# kickstart_Adapter_Amiga500_Rev5.net
KiCad netlist of a schematic drawn in EAGLE
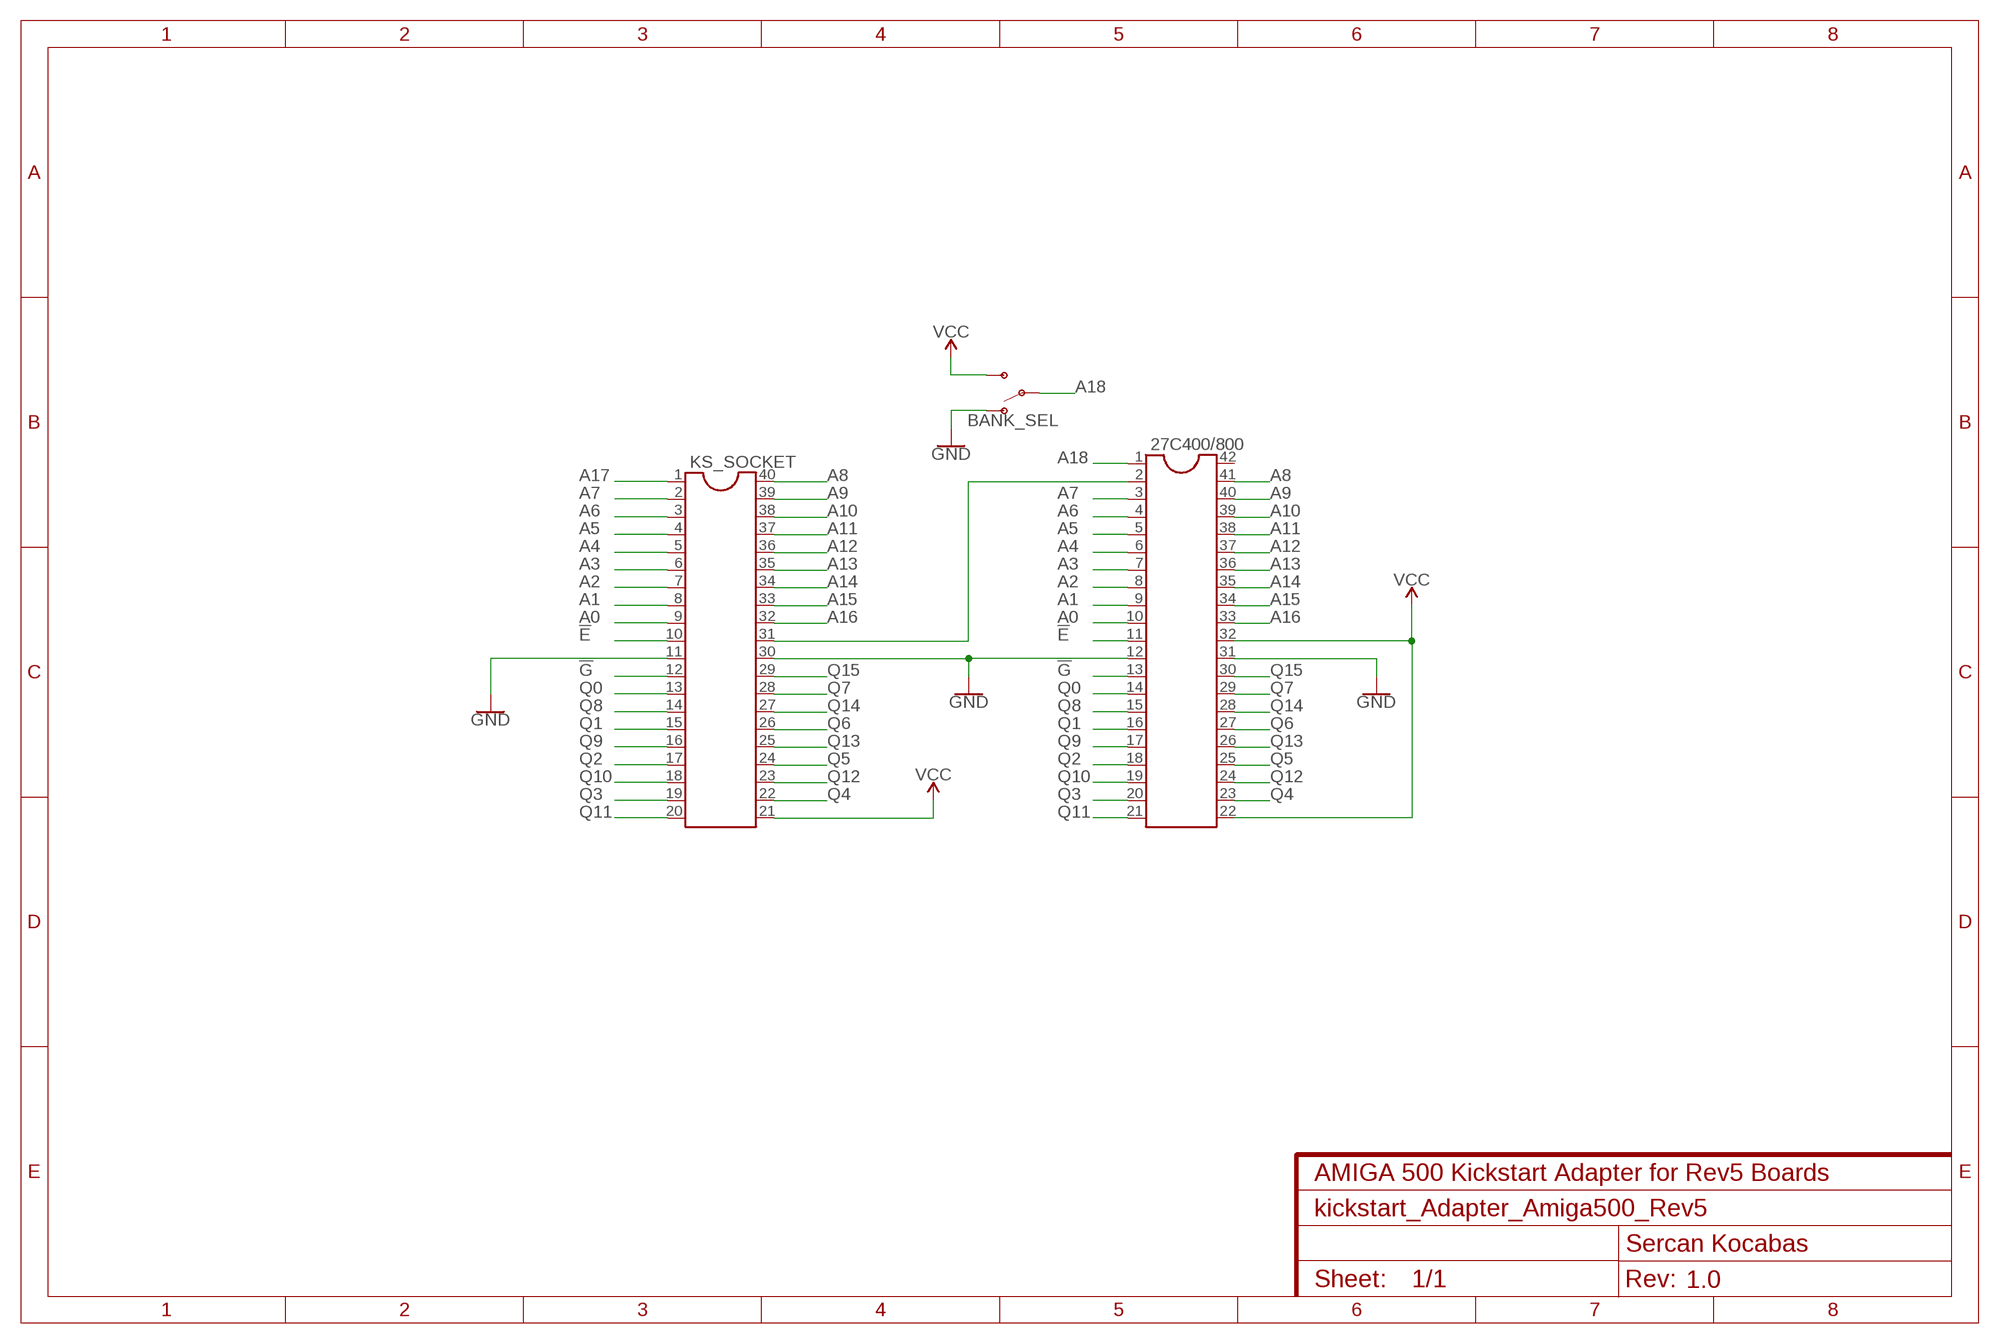
[diagram p0: schematic, sheet 1]

(export (version "E")
  (design (tool "Eeschema 10.0.6"))
  (components
    (comp (ref "27C400/800")
      (value "DIL42")
      (footprint "eagle-import:DIL42")
      (libsource (lib "eagle-import") (part "DIL42"))
    )
    (comp (ref "BANK_SEL")
      (value "SWITCH-SPDT-PTH-11.6X4.0MM")
      (footprint "eagle-import:SWITCH_SPDT_PTH_11.6X4.0MM")
      (libsource (lib "eagle-import") (part "SWITCH-SPDT-PTH-11.6X4.0MM"))
    )
    (comp (ref "KS_SOCKET")
      (value "DIL40")
      (footprint "eagle-import:DIL40")
      (libsource (lib "eagle-import") (part "DIL40"))
    )
  )
  (nets
    (net (code "1") (name "/A0") (class "Default")
      (node (ref "27C400/800") (pin "10") (pinfunction "10_10") (pintype "passive"))
      (node (ref "KS_SOCKET") (pin "9") (pinfunction "9_9") (pintype "passive"))
    )
    (net (code "2") (name "/A1") (class "Default")
      (node (ref "27C400/800") (pin "9") (pinfunction "9_9") (pintype "passive"))
      (node (ref "KS_SOCKET") (pin "8") (pinfunction "8_8") (pintype "passive"))
    )
    (net (code "3") (name "/A2") (class "Default")
      (node (ref "27C400/800") (pin "8") (pinfunction "8_8") (pintype "passive"))
      (node (ref "KS_SOCKET") (pin "7") (pinfunction "7_7") (pintype "passive"))
    )
    (net (code "4") (name "/A3") (class "Default")
      (node (ref "27C400/800") (pin "7") (pinfunction "7_7") (pintype "passive"))
      (node (ref "KS_SOCKET") (pin "6") (pinfunction "6_6") (pintype "passive"))
    )
    (net (code "5") (name "/A4") (class "Default")
      (node (ref "27C400/800") (pin "6") (pinfunction "6_6") (pintype "passive"))
      (node (ref "KS_SOCKET") (pin "5") (pinfunction "5_5") (pintype "passive"))
    )
    (net (code "6") (name "/A5") (class "Default")
      (node (ref "27C400/800") (pin "5") (pinfunction "5_5") (pintype "passive"))
      (node (ref "KS_SOCKET") (pin "4") (pinfunction "4_4") (pintype "passive"))
    )
    (net (code "7") (name "/A6") (class "Default")
      (node (ref "27C400/800") (pin "4") (pinfunction "4_4") (pintype "passive"))
      (node (ref "KS_SOCKET") (pin "3") (pinfunction "3_3") (pintype "passive"))
    )
    (net (code "8") (name "/A7") (class "Default")
      (node (ref "27C400/800") (pin "3") (pinfunction "3_3") (pintype "passive"))
      (node (ref "KS_SOCKET") (pin "2") (pinfunction "2_2") (pintype "passive"))
    )
    (net (code "9") (name "/A8") (class "Default")
      (node (ref "27C400/800") (pin "41") (pinfunction "41_41") (pintype "passive"))
      (node (ref "KS_SOCKET") (pin "40") (pinfunction "40_40") (pintype "passive"))
    )
    (net (code "10") (name "/A9") (class "Default")
      (node (ref "27C400/800") (pin "40") (pinfunction "40_40") (pintype "passive"))
      (node (ref "KS_SOCKET") (pin "39") (pinfunction "39_39") (pintype "passive"))
    )
    (net (code "11") (name "/A10") (class "Default")
      (node (ref "27C400/800") (pin "39") (pinfunction "39_39") (pintype "passive"))
      (node (ref "KS_SOCKET") (pin "38") (pinfunction "38_38") (pintype "passive"))
    )
    (net (code "12") (name "/A11") (class "Default")
      (node (ref "27C400/800") (pin "38") (pinfunction "38_38") (pintype "passive"))
      (node (ref "KS_SOCKET") (pin "37") (pinfunction "37_37") (pintype "passive"))
    )
    (net (code "13") (name "/A12") (class "Default")
      (node (ref "27C400/800") (pin "37") (pinfunction "37_37") (pintype "passive"))
      (node (ref "KS_SOCKET") (pin "36") (pinfunction "36_36") (pintype "passive"))
    )
    (net (code "14") (name "/A13") (class "Default")
      (node (ref "27C400/800") (pin "36") (pinfunction "36_36") (pintype "passive"))
      (node (ref "KS_SOCKET") (pin "35") (pinfunction "35_35") (pintype "passive"))
    )
    (net (code "15") (name "/A14") (class "Default")
      (node (ref "27C400/800") (pin "35") (pinfunction "35_35") (pintype "passive"))
      (node (ref "KS_SOCKET") (pin "34") (pinfunction "34_34") (pintype "passive"))
    )
    (net (code "16") (name "/A15") (class "Default")
      (node (ref "27C400/800") (pin "34") (pinfunction "34_34") (pintype "passive"))
      (node (ref "KS_SOCKET") (pin "33") (pinfunction "33_33") (pintype "passive"))
    )
    (net (code "17") (name "/A16") (class "Default")
      (node (ref "27C400/800") (pin "33") (pinfunction "33_33") (pintype "passive"))
      (node (ref "KS_SOCKET") (pin "32") (pinfunction "32_32") (pintype "passive"))
    )
    (net (code "18") (name "/A17") (class "Default")
      (node (ref "27C400/800") (pin "2") (pinfunction "2_2") (pintype "passive"))
      (node (ref "KS_SOCKET") (pin "1") (pinfunction "1_1") (pintype "passive"))
      (node (ref "KS_SOCKET") (pin "31") (pinfunction "31_31") (pintype "passive"))
    )
    (net (code "19") (name "/A18") (class "Default")
      (node (ref "27C400/800") (pin "1") (pinfunction "1_1") (pintype "passive"))
      (node (ref "BANK_SEL") (pin "2") (pinfunction "P_2") (pintype "passive"))
    )
    (net (code "20") (name "/Q0") (class "Default")
      (node (ref "27C400/800") (pin "14") (pinfunction "14_14") (pintype "passive"))
      (node (ref "KS_SOCKET") (pin "13") (pinfunction "13_13") (pintype "passive"))
    )
    (net (code "21") (name "/Q1") (class "Default")
      (node (ref "27C400/800") (pin "16") (pinfunction "16_16") (pintype "passive"))
      (node (ref "KS_SOCKET") (pin "15") (pinfunction "15_15") (pintype "passive"))
    )
    (net (code "22") (name "/Q2") (class "Default")
      (node (ref "27C400/800") (pin "18") (pinfunction "18_18") (pintype "passive"))
      (node (ref "KS_SOCKET") (pin "17") (pinfunction "17_17") (pintype "passive"))
    )
    (net (code "23") (name "/Q3") (class "Default")
      (node (ref "27C400/800") (pin "20") (pinfunction "20_20") (pintype "passive"))
      (node (ref "KS_SOCKET") (pin "19") (pinfunction "19_19") (pintype "passive"))
    )
    (net (code "24") (name "/Q4") (class "Default")
      (node (ref "27C400/800") (pin "23") (pinfunction "23_23") (pintype "passive"))
      (node (ref "KS_SOCKET") (pin "22") (pinfunction "22_22") (pintype "passive"))
    )
    (net (code "25") (name "/Q5") (class "Default")
      (node (ref "27C400/800") (pin "25") (pinfunction "25_25") (pintype "passive"))
      (node (ref "KS_SOCKET") (pin "24") (pinfunction "24_24") (pintype "passive"))
    )
    (net (code "26") (name "/Q6") (class "Default")
      (node (ref "27C400/800") (pin "27") (pinfunction "27_27") (pintype "passive"))
      (node (ref "KS_SOCKET") (pin "26") (pinfunction "26_26") (pintype "passive"))
    )
    (net (code "27") (name "/Q7") (class "Default")
      (node (ref "27C400/800") (pin "29") (pinfunction "29_29") (pintype "passive"))
      (node (ref "KS_SOCKET") (pin "28") (pinfunction "28_28") (pintype "passive"))
    )
    (net (code "28") (name "/Q8") (class "Default")
      (node (ref "27C400/800") (pin "15") (pinfunction "15_15") (pintype "passive"))
      (node (ref "KS_SOCKET") (pin "14") (pinfunction "14_14") (pintype "passive"))
    )
    (net (code "29") (name "/Q9") (class "Default")
      (node (ref "27C400/800") (pin "17") (pinfunction "17_17") (pintype "passive"))
      (node (ref "KS_SOCKET") (pin "16") (pinfunction "16_16") (pintype "passive"))
    )
    (net (code "30") (name "/Q10") (class "Default")
      (node (ref "27C400/800") (pin "19") (pinfunction "19_19") (pintype "passive"))
      (node (ref "KS_SOCKET") (pin "18") (pinfunction "18_18") (pintype "passive"))
    )
    (net (code "31") (name "/Q11") (class "Default")
      (node (ref "27C400/800") (pin "21") (pinfunction "21_21") (pintype "passive"))
      (node (ref "KS_SOCKET") (pin "20") (pinfunction "20_20") (pintype "passive"))
    )
    (net (code "32") (name "/Q12") (class "Default")
      (node (ref "27C400/800") (pin "24") (pinfunction "24_24") (pintype "passive"))
      (node (ref "KS_SOCKET") (pin "23") (pinfunction "23_23") (pintype "passive"))
    )
    (net (code "33") (name "/Q13") (class "Default")
      (node (ref "27C400/800") (pin "26") (pinfunction "26_26") (pintype "passive"))
      (node (ref "KS_SOCKET") (pin "25") (pinfunction "25_25") (pintype "passive"))
    )
    (net (code "34") (name "/Q14") (class "Default")
      (node (ref "27C400/800") (pin "28") (pinfunction "28_28") (pintype "passive"))
      (node (ref "KS_SOCKET") (pin "27") (pinfunction "27_27") (pintype "passive"))
    )
    (net (code "35") (name "/Q15") (class "Default")
      (node (ref "27C400/800") (pin "30") (pinfunction "30_30") (pintype "passive"))
      (node (ref "KS_SOCKET") (pin "29") (pinfunction "29_29") (pintype "passive"))
    )
    (net (code "36") (name "/~{E}") (class "Default")
      (node (ref "27C400/800") (pin "11") (pinfunction "11_11") (pintype "passive"))
      (node (ref "KS_SOCKET") (pin "10") (pinfunction "10_10") (pintype "passive"))
    )
    (net (code "37") (name "/~{G}") (class "Default")
      (node (ref "27C400/800") (pin "13") (pinfunction "13_13") (pintype "passive"))
      (node (ref "KS_SOCKET") (pin "12") (pinfunction "12_12") (pintype "passive"))
    )
    (net (code "38") (name "GND") (class "Default")
      (node (ref "27C400/800") (pin "12") (pinfunction "12_12") (pintype "passive"))
      (node (ref "27C400/800") (pin "31") (pinfunction "31_31") (pintype "passive"))
      (node (ref "BANK_SEL") (pin "1") (pinfunction "O_1") (pintype "passive"))
      (node (ref "KS_SOCKET") (pin "11") (pinfunction "11_11") (pintype "passive"))
      (node (ref "KS_SOCKET") (pin "30") (pinfunction "30_30") (pintype "passive"))
    )
    (net (code "39") (name "VCC") (class "Default")
      (node (ref "27C400/800") (pin "22") (pinfunction "22_22") (pintype "passive"))
      (node (ref "27C400/800") (pin "32") (pinfunction "32_32") (pintype "passive"))
      (node (ref "BANK_SEL") (pin "3") (pinfunction "S_3") (pintype "passive"))
      (node (ref "KS_SOCKET") (pin "21") (pinfunction "21_21") (pintype "passive"))
    )
    (net (code "40") (name "unconnected-(27C400/800-Pad42)") (class "Default")
      (node (ref "27C400/800") (pin "42") (pinfunction "42_42") (pintype "passive"))
    )
  )
)
